# WLS2.net
KiCad netlist of a schematic drawn in EAGLE
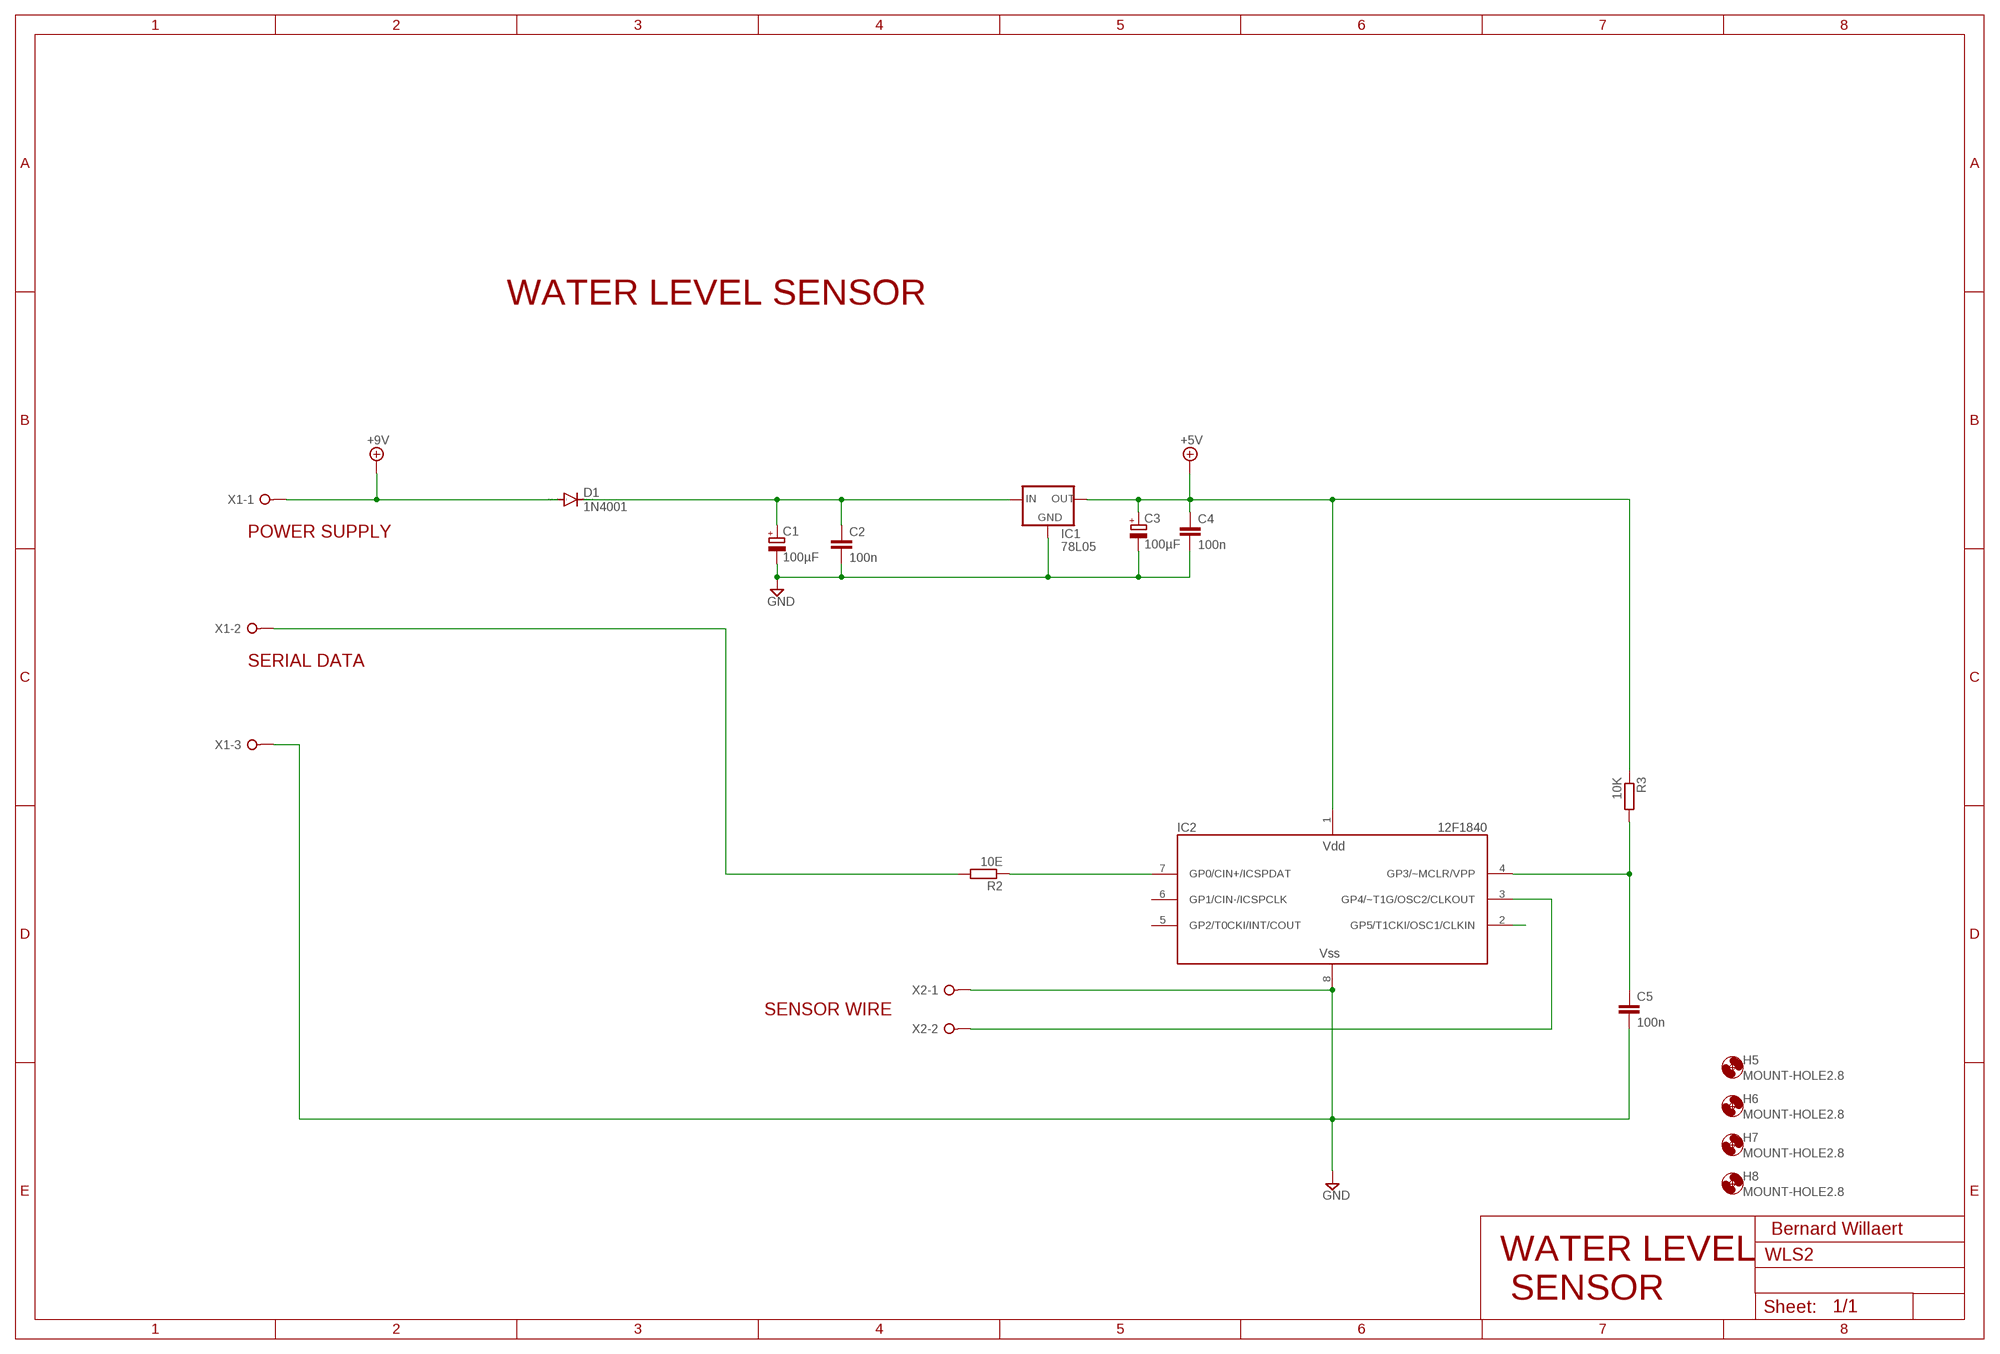
[diagram p0: schematic, sheet 1]

(export (version "E")
  (design (tool "Eeschema 10.0.6"))
  (components
    (comp (ref "C1")
      (value "100µF")
      (footprint "eagle-import:E5-6")
      (libsource (lib "eagle-import") (part "CPOL-EUE5-6"))
    )
    (comp (ref "C2")
      (value "100n")
      (footprint "eagle-import:C050-025X075")
      (libsource (lib "eagle-import") (part "C-EU050-025X075"))
    )
    (comp (ref "C3")
      (value "100µF")
      (footprint "eagle-import:E5-6")
      (libsource (lib "eagle-import") (part "CPOL-EUE5-6"))
    )
    (comp (ref "C4")
      (value "100n")
      (footprint "eagle-import:C050-025X075")
      (libsource (lib "eagle-import") (part "C-EU050-025X075"))
    )
    (comp (ref "C5")
      (value "100n")
      (footprint "eagle-import:C050-025X075")
      (libsource (lib "eagle-import") (part "C-EU050-025X075"))
    )
    (comp (ref "D1")
      (value "1N4001")
      (footprint "eagle-import:DO41-10")
      (libsource (lib "eagle-import") (part "1N4004"))
    )
    (comp (ref "H5")
      (value "MOUNT-HOLE2.8")
      (footprint "eagle-import:2,8")
      (libsource (lib "eagle-import") (part "MOUNT-HOLE2.8"))
    )
    (comp (ref "H6")
      (value "MOUNT-HOLE2.8")
      (footprint "eagle-import:2,8")
      (libsource (lib "eagle-import") (part "MOUNT-HOLE2.8"))
    )
    (comp (ref "H7")
      (value "MOUNT-HOLE2.8")
      (footprint "eagle-import:2,8")
      (libsource (lib "eagle-import") (part "MOUNT-HOLE2.8"))
    )
    (comp (ref "H8")
      (value "MOUNT-HOLE2.8")
      (footprint "eagle-import:2,8")
      (libsource (lib "eagle-import") (part "MOUNT-HOLE2.8"))
    )
    (comp (ref "IC1")
      (value "78L05")
      (footprint "eagle-import:78LXX")
      (libsource (lib "eagle-import") (part "78LXX"))
    )
    (comp (ref "IC2")
      (value "12F1840")
      (footprint "eagle-import:DIP-8")
      (libsource (lib "eagle-import") (part "PIC12F629P"))
    )
    (comp (ref "R2")
      (value "10E")
      (footprint "eagle-import:0207_10")
      (libsource (lib "eagle-import") (part "R-EU_0207/10"))
    )
    (comp (ref "R3")
      (value "10K")
      (footprint "eagle-import:0207_10")
      (libsource (lib "eagle-import") (part "R-EU_0207/10"))
    )
    (comp (ref "X1")
      (value "W237-03P")
      (footprint "eagle-import:W237-133")
      (libsource (lib "eagle-import") (part "W237-03P"))
    )
    (comp (ref "X2")
      (value "W237-02P")
      (footprint "eagle-import:W237-132")
      (libsource (lib "eagle-import") (part "W237-02P"))
    )
  )
  (nets
    (net (code "1") (name "+5V") (class "Default")
      (node (ref "C3") (pin "+") (pinfunction "+_+") (pintype "passive"))
      (node (ref "C4") (pin "1") (pinfunction "1_1") (pintype "passive"))
      (node (ref "IC1") (pin "OUT") (pinfunction "OUT_OUT") (pintype "passive"))
      (node (ref "IC2") (pin "1") (pinfunction "VDD_1") (pintype "power_in"))
      (node (ref "R3") (pin "1") (pinfunction "1_1") (pintype "passive"))
    )
    (net (code "2") (name "+9V") (class "Default")
      (node (ref "D1") (pin "A") (pinfunction "A_A") (pintype "passive"))
      (node (ref "X1") (pin "1") (pinfunction "KL_1") (pintype "passive"))
    )
    (net (code "3") (name "GND") (class "Default")
      (node (ref "C1") (pin "-") (pinfunction "-_-") (pintype "passive"))
      (node (ref "C2") (pin "2") (pinfunction "2_2") (pintype "passive"))
      (node (ref "C3") (pin "-") (pinfunction "-_-") (pintype "passive"))
      (node (ref "C4") (pin "2") (pinfunction "2_2") (pintype "passive"))
      (node (ref "C5") (pin "2") (pinfunction "2_2") (pintype "passive"))
      (node (ref "IC1") (pin "GND") (pinfunction "GND_GND") (pintype "input"))
      (node (ref "IC2") (pin "8") (pinfunction "VSS_8") (pintype "power_in"))
      (node (ref "X1") (pin "3") (pinfunction "KL_3") (pintype "passive"))
      (node (ref "X2") (pin "1") (pinfunction "KL_1") (pintype "passive"))
    )
    (net (code "4") (name "Net-(C1-Pad+)") (class "Default")
      (node (ref "C1") (pin "+") (pinfunction "+_+") (pintype "passive"))
      (node (ref "C2") (pin "1") (pinfunction "1_1") (pintype "passive"))
      (node (ref "D1") (pin "C") (pinfunction "C_C") (pintype "passive"))
      (node (ref "IC1") (pin "IN") (pinfunction "IN_IN") (pintype "input"))
    )
    (net (code "5") (name "Net-(IC2-GP0{slash}CIN+{slash}ICSPDAT)") (class "Default")
      (node (ref "IC2") (pin "7") (pinfunction "GP0/CIN+/ICSPDAT_7") (pintype "bidirectional"))
      (node (ref "R2") (pin "1") (pinfunction "1_1") (pintype "passive"))
    )
    (net (code "6") (name "Net-(IC2-GP3{slash}~{MCLR{slash}VPP})") (class "Default")
      (node (ref "C5") (pin "1") (pinfunction "1_1") (pintype "passive"))
      (node (ref "IC2") (pin "4") (pinfunction "GP3/~{MCLR/VPP}_4") (pintype "input"))
      (node (ref "R3") (pin "2") (pinfunction "2_2") (pintype "passive"))
    )
    (net (code "7") (name "Net-(IC2-GP4{slash}~{T1G{slash}OSC2{slash}CLKOUT})") (class "Default")
      (node (ref "IC2") (pin "3") (pinfunction "GP4/~{T1G/OSC2/CLKOUT}_3") (pintype "bidirectional"))
      (node (ref "X2") (pin "2") (pinfunction "KL_2") (pintype "passive"))
    )
    (net (code "8") (name "Net-(X1B-KL)") (class "Default")
      (node (ref "R2") (pin "2") (pinfunction "2_2") (pintype "passive"))
      (node (ref "X1") (pin "2") (pinfunction "KL_2") (pintype "passive"))
    )
    (net (code "9") (name "unconnected-(IC2-GP1{slash}CIN-{slash}ICSPCLK-Pad6)") (class "Default")
      (node (ref "IC2") (pin "6") (pinfunction "GP1/CIN-/ICSPCLK_6") (pintype "bidirectional"))
    )
    (net (code "10") (name "unconnected-(IC2-GP2{slash}T0CKI{slash}INT{slash}COUT-Pad5)") (class "Default")
      (node (ref "IC2") (pin "5") (pinfunction "GP2/T0CKI/INT/COUT_5") (pintype "bidirectional"))
    )
    (net (code "11") (name "unconnected-(IC2-GP5{slash}T1CKI{slash}OSC1{slash}CLKIN-Pad2)") (class "Default")
      (node (ref "IC2") (pin "2") (pinfunction "GP5/T1CKI/OSC1/CLKIN_2") (pintype "bidirectional"))
    )
  )
)
